# CYPRESS_SRAM_DB.net
KiCad netlist of a schematic drawn in EAGLE
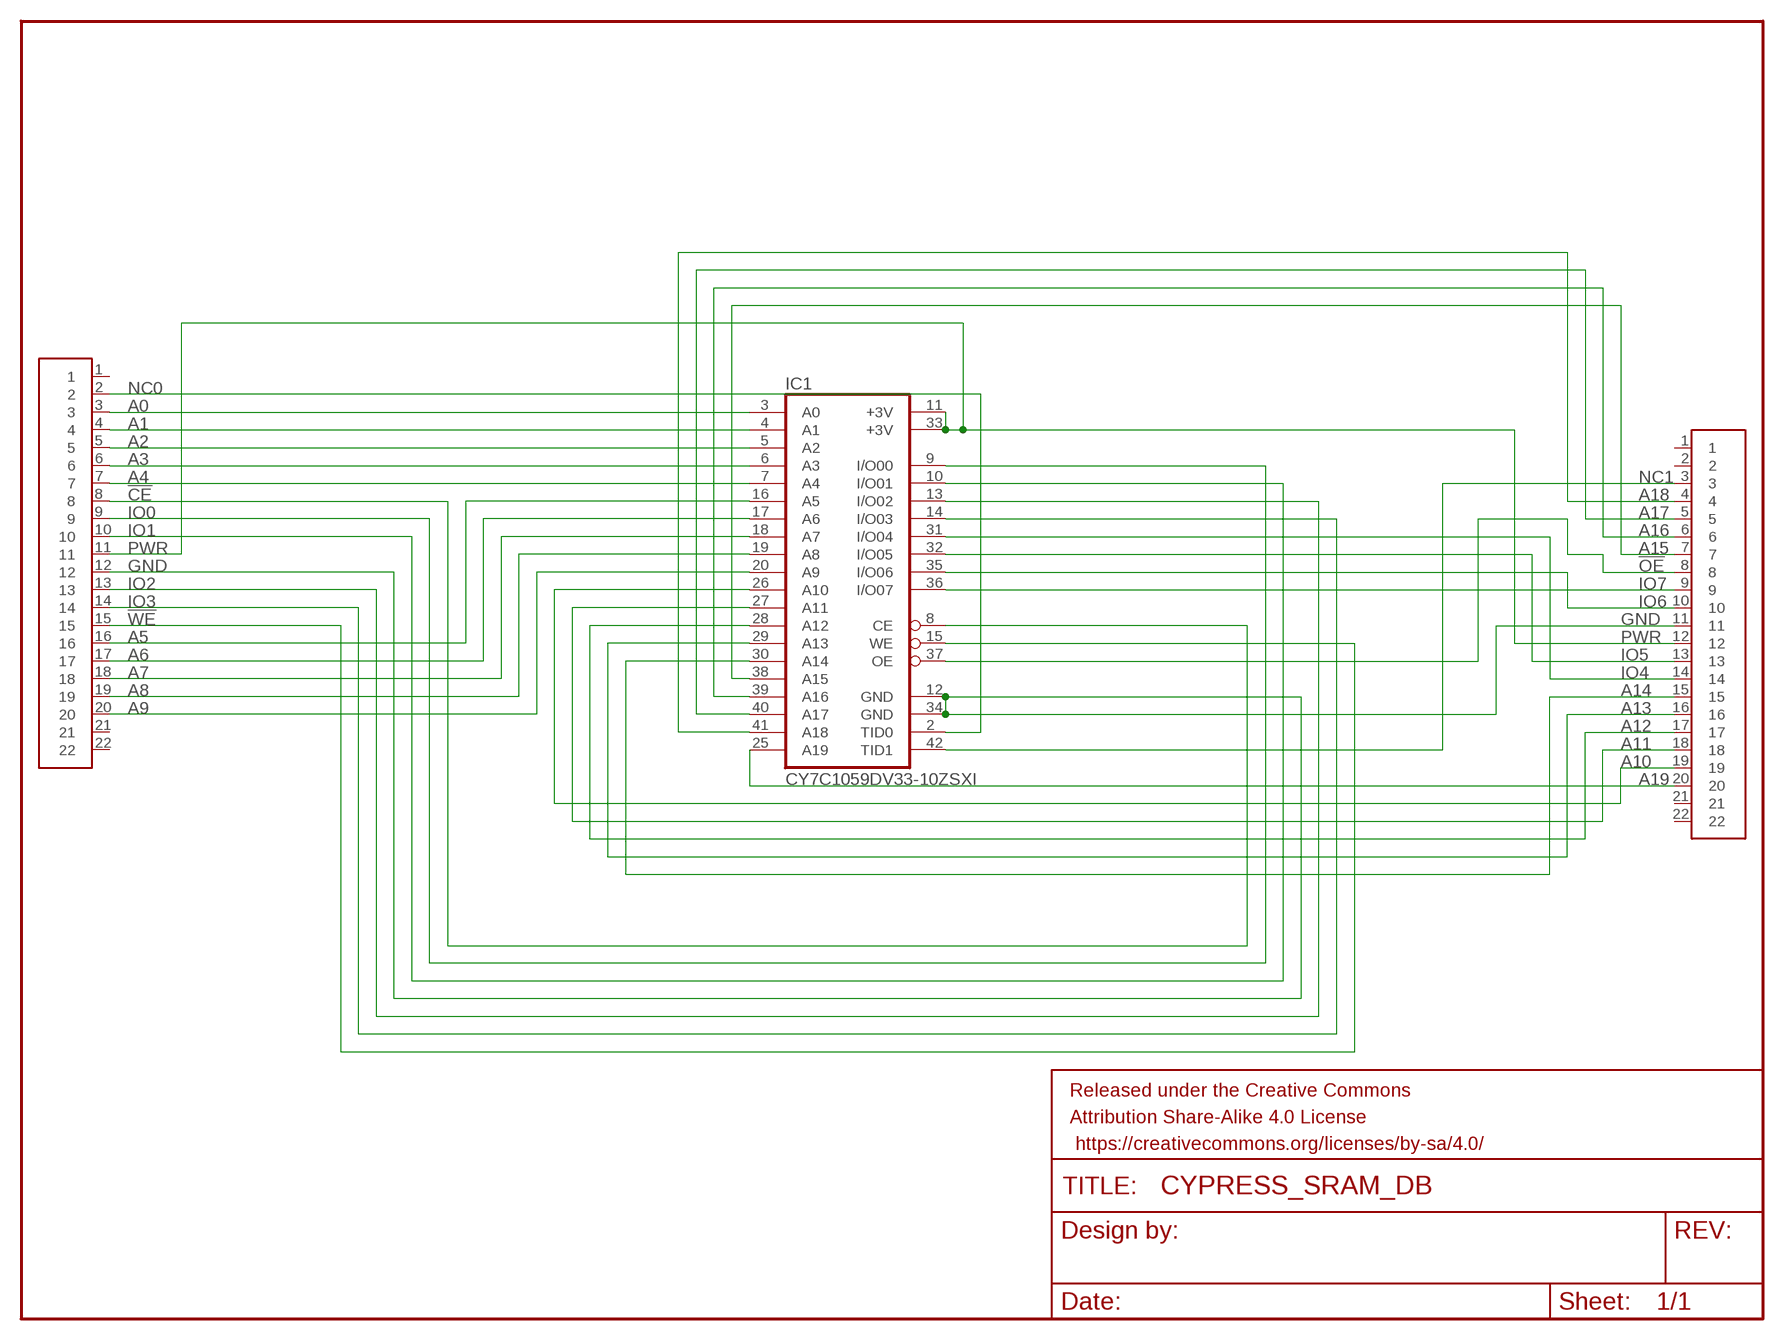
[diagram p0: schematic, sheet 1]

(export (version "E")
  (design (tool "Eeschema 10.0.6"))
  (components
    (comp (ref "FRAME1")
      (value "FRAME-LETTERNO_PACKAGE")
      (footprint "eagle-import:DUMMY")
      (fields (field (name "DESIGNER") "Nobody"))
      (libsource (lib "eagle-import") (part "FRAME-LETTERNO_PACKAGE"))
    )
    (comp (ref "IC1")
      (value "CY7C1059DV33-10ZSXI")
      (footprint "eagle-import:TSOPII-Z44")
      (libsource (lib "eagle-import") (part "CY7C1059DV33-10ZSXI"))
    )
    (comp (ref "U$1")
      (value "1X22THM")
      (footprint "eagle-import:1X22")
      (libsource (lib "eagle-import") (part "1X22THM"))
    )
    (comp (ref "U$2")
      (value "1X22THM")
      (footprint "eagle-import:1X22")
      (libsource (lib "eagle-import") (part "1X22THM"))
    )
  )
  (nets
    (net (code "1") (name "/A0") (class "Default")
      (node (ref "IC1") (pin "3") (pinfunction "A0_3") (pintype "input"))
      (node (ref "U$2") (pin "3") (pinfunction "3_3") (pintype "bidirectional"))
    )
    (net (code "2") (name "/A1") (class "Default")
      (node (ref "IC1") (pin "4") (pinfunction "A1_4") (pintype "input"))
      (node (ref "U$2") (pin "4") (pinfunction "4_4") (pintype "bidirectional"))
    )
    (net (code "3") (name "/A2") (class "Default")
      (node (ref "IC1") (pin "5") (pinfunction "A2_5") (pintype "input"))
      (node (ref "U$2") (pin "5") (pinfunction "5_5") (pintype "bidirectional"))
    )
    (net (code "4") (name "/A3") (class "Default")
      (node (ref "IC1") (pin "6") (pinfunction "A3_6") (pintype "input"))
      (node (ref "U$2") (pin "6") (pinfunction "6_6") (pintype "bidirectional"))
    )
    (net (code "5") (name "/A4") (class "Default")
      (node (ref "IC1") (pin "7") (pinfunction "A4_7") (pintype "input"))
      (node (ref "U$2") (pin "7") (pinfunction "7_7") (pintype "bidirectional"))
    )
    (net (code "6") (name "/A5") (class "Default")
      (node (ref "IC1") (pin "16") (pinfunction "A5_16") (pintype "input"))
      (node (ref "U$2") (pin "16") (pinfunction "16_16") (pintype "bidirectional"))
    )
    (net (code "7") (name "/A6") (class "Default")
      (node (ref "IC1") (pin "17") (pinfunction "A6_17") (pintype "input"))
      (node (ref "U$2") (pin "17") (pinfunction "17_17") (pintype "bidirectional"))
    )
    (net (code "8") (name "/A7") (class "Default")
      (node (ref "IC1") (pin "18") (pinfunction "A7_18") (pintype "input"))
      (node (ref "U$2") (pin "18") (pinfunction "18_18") (pintype "bidirectional"))
    )
    (net (code "9") (name "/A8") (class "Default")
      (node (ref "IC1") (pin "19") (pinfunction "A8_19") (pintype "input"))
      (node (ref "U$2") (pin "19") (pinfunction "19_19") (pintype "bidirectional"))
    )
    (net (code "10") (name "/A9") (class "Default")
      (node (ref "IC1") (pin "20") (pinfunction "A9_20") (pintype "input"))
      (node (ref "U$2") (pin "20") (pinfunction "20_20") (pintype "bidirectional"))
    )
    (net (code "11") (name "/A10") (class "Default")
      (node (ref "IC1") (pin "26") (pinfunction "A10_26") (pintype "input"))
      (node (ref "U$1") (pin "19") (pinfunction "19_19") (pintype "bidirectional"))
    )
    (net (code "12") (name "/A11") (class "Default")
      (node (ref "IC1") (pin "27") (pinfunction "A11_27") (pintype "input"))
      (node (ref "U$1") (pin "18") (pinfunction "18_18") (pintype "bidirectional"))
    )
    (net (code "13") (name "/A12") (class "Default")
      (node (ref "IC1") (pin "28") (pinfunction "A12_28") (pintype "input"))
      (node (ref "U$1") (pin "17") (pinfunction "17_17") (pintype "bidirectional"))
    )
    (net (code "14") (name "/A13") (class "Default")
      (node (ref "IC1") (pin "29") (pinfunction "A13_29") (pintype "input"))
      (node (ref "U$1") (pin "16") (pinfunction "16_16") (pintype "bidirectional"))
    )
    (net (code "15") (name "/A14") (class "Default")
      (node (ref "IC1") (pin "30") (pinfunction "A14_30") (pintype "input"))
      (node (ref "U$1") (pin "15") (pinfunction "15_15") (pintype "bidirectional"))
    )
    (net (code "16") (name "/A15") (class "Default")
      (node (ref "IC1") (pin "38") (pinfunction "A15_38") (pintype "input"))
      (node (ref "U$1") (pin "7") (pinfunction "7_7") (pintype "bidirectional"))
    )
    (net (code "17") (name "/A16") (class "Default")
      (node (ref "IC1") (pin "39") (pinfunction "A16_39") (pintype "input"))
      (node (ref "U$1") (pin "6") (pinfunction "6_6") (pintype "bidirectional"))
    )
    (net (code "18") (name "/A17") (class "Default")
      (node (ref "IC1") (pin "40") (pinfunction "A17_40") (pintype "input"))
      (node (ref "U$1") (pin "5") (pinfunction "5_5") (pintype "bidirectional"))
    )
    (net (code "19") (name "/A18") (class "Default")
      (node (ref "IC1") (pin "41") (pinfunction "A18_41") (pintype "input"))
      (node (ref "U$1") (pin "4") (pinfunction "4_4") (pintype "bidirectional"))
    )
    (net (code "20") (name "/A19") (class "Default")
      (node (ref "IC1") (pin "25") (pinfunction "A19_25") (pintype "input"))
      (node (ref "U$1") (pin "20") (pinfunction "20_20") (pintype "bidirectional"))
    )
    (net (code "21") (name "/GND") (class "Default")
      (node (ref "IC1") (pin "12") (pinfunction "GND_12") (pintype "power_in"))
      (node (ref "IC1") (pin "34") (pinfunction "GND_34") (pintype "power_in"))
      (node (ref "U$1") (pin "11") (pinfunction "11_11") (pintype "bidirectional"))
      (node (ref "U$2") (pin "12") (pinfunction "12_12") (pintype "bidirectional"))
    )
    (net (code "22") (name "/IO0") (class "Default")
      (node (ref "IC1") (pin "9") (pinfunction "I/O00_9") (pintype "bidirectional"))
      (node (ref "U$2") (pin "9") (pinfunction "9_9") (pintype "bidirectional"))
    )
    (net (code "23") (name "/IO1") (class "Default")
      (node (ref "IC1") (pin "10") (pinfunction "I/O01_10") (pintype "bidirectional"))
      (node (ref "U$2") (pin "10") (pinfunction "10_10") (pintype "bidirectional"))
    )
    (net (code "24") (name "/IO2") (class "Default")
      (node (ref "IC1") (pin "13") (pinfunction "I/O02_13") (pintype "bidirectional"))
      (node (ref "U$2") (pin "13") (pinfunction "13_13") (pintype "bidirectional"))
    )
    (net (code "25") (name "/IO3") (class "Default")
      (node (ref "IC1") (pin "14") (pinfunction "I/O03_14") (pintype "bidirectional"))
      (node (ref "U$2") (pin "14") (pinfunction "14_14") (pintype "bidirectional"))
    )
    (net (code "26") (name "/IO4") (class "Default")
      (node (ref "IC1") (pin "31") (pinfunction "I/O04_31") (pintype "bidirectional"))
      (node (ref "U$1") (pin "14") (pinfunction "14_14") (pintype "bidirectional"))
    )
    (net (code "27") (name "/IO5") (class "Default")
      (node (ref "IC1") (pin "32") (pinfunction "I/O05_32") (pintype "bidirectional"))
      (node (ref "U$1") (pin "13") (pinfunction "13_13") (pintype "bidirectional"))
    )
    (net (code "28") (name "/IO6") (class "Default")
      (node (ref "IC1") (pin "35") (pinfunction "I/O06_35") (pintype "bidirectional"))
      (node (ref "U$1") (pin "10") (pinfunction "10_10") (pintype "bidirectional"))
    )
    (net (code "29") (name "/IO7") (class "Default")
      (node (ref "IC1") (pin "36") (pinfunction "I/O07_36") (pintype "bidirectional"))
      (node (ref "U$1") (pin "9") (pinfunction "9_9") (pintype "bidirectional"))
    )
    (net (code "30") (name "/NC0") (class "Default")
      (node (ref "IC1") (pin "2") (pinfunction "TID0_2") (pintype "bidirectional"))
      (node (ref "U$2") (pin "2") (pinfunction "2_2") (pintype "bidirectional"))
    )
    (net (code "31") (name "/NC1") (class "Default")
      (node (ref "IC1") (pin "42") (pinfunction "TID1_42") (pintype "bidirectional"))
      (node (ref "U$1") (pin "3") (pinfunction "3_3") (pintype "bidirectional"))
    )
    (net (code "32") (name "/PWR") (class "Default")
      (node (ref "IC1") (pin "11") (pinfunction "+3V_11") (pintype "power_in"))
      (node (ref "IC1") (pin "33") (pinfunction "+3V_33") (pintype "power_in"))
      (node (ref "U$1") (pin "12") (pinfunction "12_12") (pintype "bidirectional"))
      (node (ref "U$2") (pin "11") (pinfunction "11_11") (pintype "bidirectional"))
    )
    (net (code "33") (name "/~{CE}") (class "Default")
      (node (ref "IC1") (pin "8") (pinfunction "CE_8") (pintype "input"))
      (node (ref "U$2") (pin "8") (pinfunction "8_8") (pintype "bidirectional"))
    )
    (net (code "34") (name "/~{OE}") (class "Default")
      (node (ref "IC1") (pin "37") (pinfunction "OE_37") (pintype "input"))
      (node (ref "U$1") (pin "8") (pinfunction "8_8") (pintype "bidirectional"))
    )
    (net (code "35") (name "/~{WE}") (class "Default")
      (node (ref "IC1") (pin "15") (pinfunction "WE_15") (pintype "input"))
      (node (ref "U$2") (pin "15") (pinfunction "15_15") (pintype "bidirectional"))
    )
    (net (code "36") (name "unconnected-(U$1-Pad1)") (class "Default")
      (node (ref "U$1") (pin "1") (pinfunction "1_1") (pintype "bidirectional"))
    )
    (net (code "37") (name "unconnected-(U$1-Pad2)") (class "Default")
      (node (ref "U$1") (pin "2") (pinfunction "2_2") (pintype "bidirectional"))
    )
    (net (code "38") (name "unconnected-(U$1-Pad21)") (class "Default")
      (node (ref "U$1") (pin "21") (pinfunction "21_21") (pintype "bidirectional"))
    )
    (net (code "39") (name "unconnected-(U$1-Pad22)") (class "Default")
      (node (ref "U$1") (pin "22") (pinfunction "22_22") (pintype "bidirectional"))
    )
    (net (code "40") (name "unconnected-(U$2-Pad1)") (class "Default")
      (node (ref "U$2") (pin "1") (pinfunction "1_1") (pintype "bidirectional"))
    )
    (net (code "41") (name "unconnected-(U$2-Pad21)") (class "Default")
      (node (ref "U$2") (pin "21") (pinfunction "21_21") (pintype "bidirectional"))
    )
    (net (code "42") (name "unconnected-(U$2-Pad22)") (class "Default")
      (node (ref "U$2") (pin "22") (pinfunction "22_22") (pintype "bidirectional"))
    )
  )
)
